# DMX_Control_Module.net
KiCad netlist of a schematic drawn in EAGLE
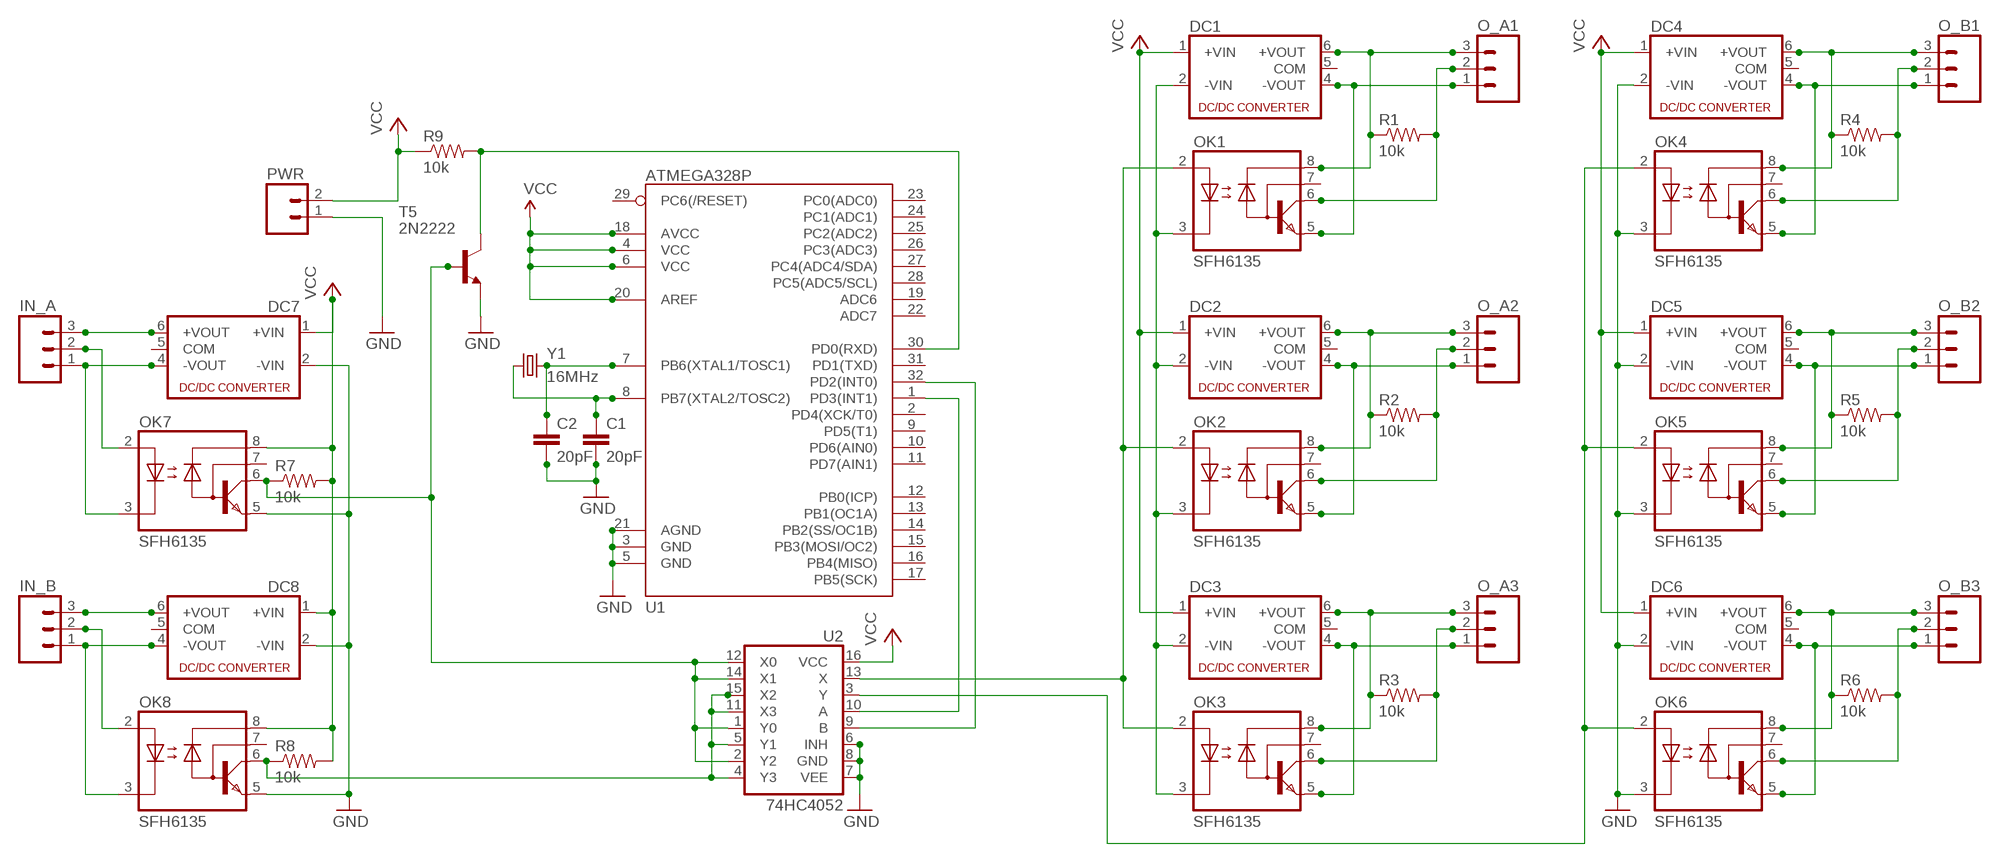
[diagram p0: schematic, sheet 1]

(export (version "E")
  (design (tool "Eeschema 10.0.6"))
  (components
    (comp (ref "C1")
      (value "20pF")
      (footprint "eagle-import:CAP-PTH-SMALL")
      (libsource (lib "eagle-import") (part "CAPPTH"))
    )
    (comp (ref "C2")
      (value "20pF")
      (footprint "eagle-import:CAP-PTH-SMALL")
      (libsource (lib "eagle-import") (part "CAPPTH"))
    )
    (comp (ref "DC1")
      (value "NMA")
      (footprint "eagle-import:NMA")
      (fields (field (name "MF") "C & D TECHNOLOGIES, INC") (field (name "MPN") "NMA0515SC"))
      (libsource (lib "eagle-import") (part "NMA"))
    )
    (comp (ref "DC2")
      (value "NMA")
      (footprint "eagle-import:NMA")
      (fields (field (name "MF") "C & D TECHNOLOGIES, INC") (field (name "MPN") "NMA0515SC"))
      (libsource (lib "eagle-import") (part "NMA"))
    )
    (comp (ref "DC3")
      (value "NMA")
      (footprint "eagle-import:NMA")
      (fields (field (name "MF") "C & D TECHNOLOGIES, INC") (field (name "MPN") "NMA0515SC"))
      (libsource (lib "eagle-import") (part "NMA"))
    )
    (comp (ref "DC4")
      (value "NMA")
      (footprint "eagle-import:NMA")
      (fields (field (name "MF") "C & D TECHNOLOGIES, INC") (field (name "MPN") "NMA0515SC"))
      (libsource (lib "eagle-import") (part "NMA"))
    )
    (comp (ref "DC5")
      (value "NMA")
      (footprint "eagle-import:NMA")
      (fields (field (name "MF") "C & D TECHNOLOGIES, INC") (field (name "MPN") "NMA0515SC"))
      (libsource (lib "eagle-import") (part "NMA"))
    )
    (comp (ref "DC6")
      (value "NMA")
      (footprint "eagle-import:NMA")
      (fields (field (name "MF") "C & D TECHNOLOGIES, INC") (field (name "MPN") "NMA0515SC"))
      (libsource (lib "eagle-import") (part "NMA"))
    )
    (comp (ref "DC7")
      (value "NMA")
      (footprint "eagle-import:NMA")
      (fields (field (name "MF") "C & D TECHNOLOGIES, INC") (field (name "MPN") "NMA0515SC"))
      (libsource (lib "eagle-import") (part "NMA"))
    )
    (comp (ref "DC8")
      (value "NMA")
      (footprint "eagle-import:NMA")
      (fields (field (name "MF") "C & D TECHNOLOGIES, INC") (field (name "MPN") "NMA0515SC"))
      (libsource (lib "eagle-import") (part "NMA"))
    )
    (comp (ref "IN_A")
      (value "M03PTH")
      (footprint "eagle-import:1X03")
      (libsource (lib "eagle-import") (part "M03PTH"))
    )
    (comp (ref "IN_B")
      (value "M03PTH")
      (footprint "eagle-import:1X03")
      (libsource (lib "eagle-import") (part "M03PTH"))
    )
    (comp (ref "OK1")
      (value "SFH6135")
      (footprint "eagle-import:DIL08")
      (fields (field (name "MF") "FAIRCHILD SEMICONDUCTOR") (field (name "MPN") "6N135"))
      (libsource (lib "eagle-import") (part "6N135"))
    )
    (comp (ref "OK2")
      (value "SFH6135")
      (footprint "eagle-import:DIL08")
      (fields (field (name "MF") "FAIRCHILD SEMICONDUCTOR") (field (name "MPN") "6N135"))
      (libsource (lib "eagle-import") (part "6N135"))
    )
    (comp (ref "OK3")
      (value "SFH6135")
      (footprint "eagle-import:DIL08")
      (fields (field (name "MF") "FAIRCHILD SEMICONDUCTOR") (field (name "MPN") "6N135"))
      (libsource (lib "eagle-import") (part "6N135"))
    )
    (comp (ref "OK4")
      (value "SFH6135")
      (footprint "eagle-import:DIL08")
      (fields (field (name "MF") "FAIRCHILD SEMICONDUCTOR") (field (name "MPN") "6N135"))
      (libsource (lib "eagle-import") (part "6N135"))
    )
    (comp (ref "OK5")
      (value "SFH6135")
      (footprint "eagle-import:DIL08")
      (fields (field (name "MF") "FAIRCHILD SEMICONDUCTOR") (field (name "MPN") "6N135"))
      (libsource (lib "eagle-import") (part "6N135"))
    )
    (comp (ref "OK6")
      (value "SFH6135")
      (footprint "eagle-import:DIL08")
      (fields (field (name "MF") "FAIRCHILD SEMICONDUCTOR") (field (name "MPN") "6N135"))
      (libsource (lib "eagle-import") (part "6N135"))
    )
    (comp (ref "OK7")
      (value "SFH6135")
      (footprint "eagle-import:DIL08")
      (fields (field (name "MF") "FAIRCHILD SEMICONDUCTOR") (field (name "MPN") "6N135"))
      (libsource (lib "eagle-import") (part "6N135"))
    )
    (comp (ref "OK8")
      (value "SFH6135")
      (footprint "eagle-import:DIL08")
      (fields (field (name "MF") "FAIRCHILD SEMICONDUCTOR") (field (name "MPN") "6N135"))
      (libsource (lib "eagle-import") (part "6N135"))
    )
    (comp (ref "O_A1")
      (value "M03PTH")
      (footprint "eagle-import:1X03")
      (libsource (lib "eagle-import") (part "M03PTH"))
    )
    (comp (ref "O_A2")
      (value "M03PTH")
      (footprint "eagle-import:1X03")
      (libsource (lib "eagle-import") (part "M03PTH"))
    )
    (comp (ref "O_A3")
      (value "M03PTH")
      (footprint "eagle-import:1X03")
      (libsource (lib "eagle-import") (part "M03PTH"))
    )
    (comp (ref "O_B1")
      (value "M03PTH")
      (footprint "eagle-import:1X03")
      (libsource (lib "eagle-import") (part "M03PTH"))
    )
    (comp (ref "O_B2")
      (value "M03PTH")
      (footprint "eagle-import:1X03")
      (libsource (lib "eagle-import") (part "M03PTH"))
    )
    (comp (ref "O_B3")
      (value "M03PTH")
      (footprint "eagle-import:1X03")
      (libsource (lib "eagle-import") (part "M03PTH"))
    )
    (comp (ref "PWR")
      (value "M02PTH")
      (footprint "eagle-import:1X02")
      (libsource (lib "eagle-import") (part "M02PTH"))
    )
    (comp (ref "R1")
      (value "10k")
      (footprint "eagle-import:AXIAL-0.4")
      (libsource (lib "eagle-import") (part "RESISTORPTH-1/4W"))
    )
    (comp (ref "R2")
      (value "10k")
      (footprint "eagle-import:AXIAL-0.4")
      (libsource (lib "eagle-import") (part "RESISTORPTH-1/4W"))
    )
    (comp (ref "R3")
      (value "10k")
      (footprint "eagle-import:AXIAL-0.4")
      (libsource (lib "eagle-import") (part "RESISTORPTH-1/4W"))
    )
    (comp (ref "R4")
      (value "10k")
      (footprint "eagle-import:AXIAL-0.4")
      (libsource (lib "eagle-import") (part "RESISTORPTH-1/4W"))
    )
    (comp (ref "R5")
      (value "10k")
      (footprint "eagle-import:AXIAL-0.4")
      (libsource (lib "eagle-import") (part "RESISTORPTH-1/4W"))
    )
    (comp (ref "R6")
      (value "10k")
      (footprint "eagle-import:AXIAL-0.4")
      (libsource (lib "eagle-import") (part "RESISTORPTH-1/4W"))
    )
    (comp (ref "R7")
      (value "10k")
      (footprint "eagle-import:AXIAL-0.4")
      (libsource (lib "eagle-import") (part "RESISTORPTH-1/4W"))
    )
    (comp (ref "R8")
      (value "10k")
      (footprint "eagle-import:AXIAL-0.4")
      (libsource (lib "eagle-import") (part "RESISTORPTH-1/4W"))
    )
    (comp (ref "R9")
      (value "10k")
      (footprint "eagle-import:AXIAL-0.4")
      (libsource (lib "eagle-import") (part "RESISTORPTH-1/4W"))
    )
    (comp (ref "T5")
      (value "2N2222")
      (footprint "eagle-import:TO92")
      (libsource (lib "eagle-import") (part "-NPN-TO92"))
    )
    (comp (ref "U1")
      (value "ATMEGA328P")
      (footprint "eagle-import:TQFP32-08")
      (libsource (lib "eagle-import") (part "ATMEGA328_SMT"))
    )
    (comp (ref "U2")
      (value "74HC4052")
      (footprint "eagle-import:DIL16")
      (libsource (lib "eagle-import") (part "74HC4052DIP"))
    )
    (comp (ref "Y1")
      (value "16MHz")
      (footprint "eagle-import:HC49US")
      (libsource (lib "eagle-import") (part "CRYSTALHC49US"))
    )
  )
  (nets
    (net (code "1") (name "GND") (class "Default")
      (node (ref "C1") (pin "2") (pinfunction "2_2") (pintype "passive"))
      (node (ref "C2") (pin "2") (pinfunction "2_2") (pintype "passive"))
      (node (ref "DC4") (pin "2") (pinfunction "-VIN_2") (pintype "passive"))
      (node (ref "DC5") (pin "2") (pinfunction "-VIN_2") (pintype "passive"))
      (node (ref "DC6") (pin "2") (pinfunction "-VIN_2") (pintype "passive"))
      (node (ref "DC7") (pin "2") (pinfunction "-VIN_2") (pintype "passive"))
      (node (ref "DC8") (pin "2") (pinfunction "-VIN_2") (pintype "passive"))
      (node (ref "OK4") (pin "3") (pinfunction "C_3") (pintype "passive"))
      (node (ref "OK5") (pin "3") (pinfunction "C_3") (pintype "passive"))
      (node (ref "OK6") (pin "3") (pinfunction "C_3") (pintype "passive"))
      (node (ref "OK7") (pin "5") (pinfunction "GND_5") (pintype "passive"))
      (node (ref "OK8") (pin "5") (pinfunction "GND_5") (pintype "passive"))
      (node (ref "PWR") (pin "1") (pinfunction "1_1") (pintype "passive"))
      (node (ref "T5") (pin "1") (pinfunction "E_1") (pintype "passive"))
      (node (ref "U1") (pin "21") (pinfunction "AGND_21") (pintype "bidirectional"))
      (node (ref "U1") (pin "3") (pinfunction "GND_3") (pintype "bidirectional"))
      (node (ref "U1") (pin "5") (pinfunction "GND_5") (pintype "bidirectional"))
      (node (ref "U2") (pin "6") (pinfunction "INH_6") (pintype "input"))
      (node (ref "U2") (pin "7") (pinfunction "VEE_7") (pintype "power_in"))
      (node (ref "U2") (pin "8") (pinfunction "GND_8") (pintype "power_in"))
    )
    (net (code "2") (name "Net-(DC1-+VOUT)") (class "Default")
      (node (ref "DC1") (pin "6") (pinfunction "+VOUT_6") (pintype "passive"))
      (node (ref "OK1") (pin "8") (pinfunction "VCC_8") (pintype "passive"))
      (node (ref "O_A1") (pin "3") (pinfunction "3_3") (pintype "passive"))
      (node (ref "R1") (pin "P$1") (pinfunction "1_P$1") (pintype "passive"))
    )
    (net (code "3") (name "Net-(DC1--VIN)") (class "Default")
      (node (ref "DC1") (pin "2") (pinfunction "-VIN_2") (pintype "passive"))
      (node (ref "DC2") (pin "2") (pinfunction "-VIN_2") (pintype "passive"))
      (node (ref "DC3") (pin "2") (pinfunction "-VIN_2") (pintype "passive"))
      (node (ref "OK1") (pin "3") (pinfunction "C_3") (pintype "passive"))
      (node (ref "OK2") (pin "3") (pinfunction "C_3") (pintype "passive"))
      (node (ref "OK3") (pin "3") (pinfunction "C_3") (pintype "passive"))
    )
    (net (code "4") (name "Net-(DC1--VOUT)") (class "Default")
      (node (ref "DC1") (pin "4") (pinfunction "-VOUT_4") (pintype "passive"))
      (node (ref "OK1") (pin "5") (pinfunction "GND_5") (pintype "passive"))
      (node (ref "O_A1") (pin "1") (pinfunction "1_1") (pintype "passive"))
    )
    (net (code "5") (name "Net-(DC2-+VOUT)") (class "Default")
      (node (ref "DC2") (pin "6") (pinfunction "+VOUT_6") (pintype "passive"))
      (node (ref "OK2") (pin "8") (pinfunction "VCC_8") (pintype "passive"))
      (node (ref "O_A2") (pin "3") (pinfunction "3_3") (pintype "passive"))
      (node (ref "R2") (pin "P$1") (pinfunction "1_P$1") (pintype "passive"))
    )
    (net (code "6") (name "Net-(DC2--VOUT)") (class "Default")
      (node (ref "DC2") (pin "4") (pinfunction "-VOUT_4") (pintype "passive"))
      (node (ref "OK2") (pin "5") (pinfunction "GND_5") (pintype "passive"))
      (node (ref "O_A2") (pin "1") (pinfunction "1_1") (pintype "passive"))
    )
    (net (code "7") (name "Net-(DC3-+VOUT)") (class "Default")
      (node (ref "DC3") (pin "6") (pinfunction "+VOUT_6") (pintype "passive"))
      (node (ref "OK3") (pin "8") (pinfunction "VCC_8") (pintype "passive"))
      (node (ref "O_A3") (pin "3") (pinfunction "3_3") (pintype "passive"))
      (node (ref "R3") (pin "P$1") (pinfunction "1_P$1") (pintype "passive"))
    )
    (net (code "8") (name "Net-(DC3--VOUT)") (class "Default")
      (node (ref "DC3") (pin "4") (pinfunction "-VOUT_4") (pintype "passive"))
      (node (ref "OK3") (pin "5") (pinfunction "GND_5") (pintype "passive"))
      (node (ref "O_A3") (pin "1") (pinfunction "1_1") (pintype "passive"))
    )
    (net (code "9") (name "Net-(DC4-+VOUT)") (class "Default")
      (node (ref "DC4") (pin "6") (pinfunction "+VOUT_6") (pintype "passive"))
      (node (ref "OK4") (pin "8") (pinfunction "VCC_8") (pintype "passive"))
      (node (ref "O_B1") (pin "3") (pinfunction "3_3") (pintype "passive"))
      (node (ref "R4") (pin "P$1") (pinfunction "1_P$1") (pintype "passive"))
    )
    (net (code "10") (name "Net-(DC4--VOUT)") (class "Default")
      (node (ref "DC4") (pin "4") (pinfunction "-VOUT_4") (pintype "passive"))
      (node (ref "OK4") (pin "5") (pinfunction "GND_5") (pintype "passive"))
      (node (ref "O_B1") (pin "1") (pinfunction "1_1") (pintype "passive"))
    )
    (net (code "11") (name "Net-(DC5-+VOUT)") (class "Default")
      (node (ref "DC5") (pin "6") (pinfunction "+VOUT_6") (pintype "passive"))
      (node (ref "OK5") (pin "8") (pinfunction "VCC_8") (pintype "passive"))
      (node (ref "O_B2") (pin "3") (pinfunction "3_3") (pintype "passive"))
      (node (ref "R5") (pin "P$1") (pinfunction "1_P$1") (pintype "passive"))
    )
    (net (code "12") (name "Net-(DC5--VOUT)") (class "Default")
      (node (ref "DC5") (pin "4") (pinfunction "-VOUT_4") (pintype "passive"))
      (node (ref "OK5") (pin "5") (pinfunction "GND_5") (pintype "passive"))
      (node (ref "O_B2") (pin "1") (pinfunction "1_1") (pintype "passive"))
    )
    (net (code "13") (name "Net-(DC6-+VOUT)") (class "Default")
      (node (ref "DC6") (pin "6") (pinfunction "+VOUT_6") (pintype "passive"))
      (node (ref "OK6") (pin "8") (pinfunction "VCC_8") (pintype "passive"))
      (node (ref "O_B3") (pin "3") (pinfunction "3_3") (pintype "passive"))
      (node (ref "R6") (pin "P$1") (pinfunction "1_P$1") (pintype "passive"))
    )
    (net (code "14") (name "Net-(DC6--VOUT)") (class "Default")
      (node (ref "DC6") (pin "4") (pinfunction "-VOUT_4") (pintype "passive"))
      (node (ref "OK6") (pin "5") (pinfunction "GND_5") (pintype "passive"))
      (node (ref "O_B3") (pin "1") (pinfunction "1_1") (pintype "passive"))
    )
    (net (code "15") (name "Net-(DC7-+VOUT)") (class "Default")
      (node (ref "DC7") (pin "6") (pinfunction "+VOUT_6") (pintype "passive"))
      (node (ref "IN_A") (pin "3") (pinfunction "3_3") (pintype "passive"))
    )
    (net (code "16") (name "Net-(DC7--VOUT)") (class "Default")
      (node (ref "DC7") (pin "4") (pinfunction "-VOUT_4") (pintype "passive"))
      (node (ref "IN_A") (pin "1") (pinfunction "1_1") (pintype "passive"))
      (node (ref "OK7") (pin "3") (pinfunction "C_3") (pintype "passive"))
    )
    (net (code "17") (name "Net-(DC8-+VOUT)") (class "Default")
      (node (ref "DC8") (pin "6") (pinfunction "+VOUT_6") (pintype "passive"))
      (node (ref "IN_B") (pin "3") (pinfunction "3_3") (pintype "passive"))
    )
    (net (code "18") (name "Net-(DC8--VOUT)") (class "Default")
      (node (ref "DC8") (pin "4") (pinfunction "-VOUT_4") (pintype "passive"))
      (node (ref "IN_B") (pin "1") (pinfunction "1_1") (pintype "passive"))
      (node (ref "OK8") (pin "3") (pinfunction "C_3") (pintype "passive"))
    )
    (net (code "19") (name "Net-(OK1-A)") (class "Default")
      (node (ref "OK1") (pin "2") (pinfunction "A_2") (pintype "passive"))
      (node (ref "OK2") (pin "2") (pinfunction "A_2") (pintype "passive"))
      (node (ref "OK3") (pin "2") (pinfunction "A_2") (pintype "passive"))
      (node (ref "U2") (pin "13") (pinfunction "X_13") (pintype "bidirectional"))
    )
    (net (code "20") (name "Net-(OK1-VO)") (class "Default")
      (node (ref "OK1") (pin "6") (pinfunction "VO_6") (pintype "passive"))
      (node (ref "O_A1") (pin "2") (pinfunction "2_2") (pintype "passive"))
      (node (ref "R1") (pin "P$2") (pinfunction "2_P$2") (pintype "passive"))
    )
    (net (code "21") (name "Net-(OK2-VO)") (class "Default")
      (node (ref "OK2") (pin "6") (pinfunction "VO_6") (pintype "passive"))
      (node (ref "O_A2") (pin "2") (pinfunction "2_2") (pintype "passive"))
      (node (ref "R2") (pin "P$2") (pinfunction "2_P$2") (pintype "passive"))
    )
    (net (code "22") (name "Net-(OK3-VO)") (class "Default")
      (node (ref "OK3") (pin "6") (pinfunction "VO_6") (pintype "passive"))
      (node (ref "O_A3") (pin "2") (pinfunction "2_2") (pintype "passive"))
      (node (ref "R3") (pin "P$2") (pinfunction "2_P$2") (pintype "passive"))
    )
    (net (code "23") (name "Net-(OK4-A)") (class "Default")
      (node (ref "OK4") (pin "2") (pinfunction "A_2") (pintype "passive"))
      (node (ref "OK5") (pin "2") (pinfunction "A_2") (pintype "passive"))
      (node (ref "OK6") (pin "2") (pinfunction "A_2") (pintype "passive"))
      (node (ref "U2") (pin "3") (pinfunction "Y_3") (pintype "bidirectional"))
    )
    (net (code "24") (name "Net-(OK4-VO)") (class "Default")
      (node (ref "OK4") (pin "6") (pinfunction "VO_6") (pintype "passive"))
      (node (ref "O_B1") (pin "2") (pinfunction "2_2") (pintype "passive"))
      (node (ref "R4") (pin "P$2") (pinfunction "2_P$2") (pintype "passive"))
    )
    (net (code "25") (name "Net-(OK5-VO)") (class "Default")
      (node (ref "OK5") (pin "6") (pinfunction "VO_6") (pintype "passive"))
      (node (ref "O_B2") (pin "2") (pinfunction "2_2") (pintype "passive"))
      (node (ref "R5") (pin "P$2") (pinfunction "2_P$2") (pintype "passive"))
    )
    (net (code "26") (name "Net-(OK6-VO)") (class "Default")
      (node (ref "OK6") (pin "6") (pinfunction "VO_6") (pintype "passive"))
      (node (ref "O_B3") (pin "2") (pinfunction "2_2") (pintype "passive"))
      (node (ref "R6") (pin "P$2") (pinfunction "2_P$2") (pintype "passive"))
    )
    (net (code "27") (name "Net-(OK7-A)") (class "Default")
      (node (ref "IN_A") (pin "2") (pinfunction "2_2") (pintype "passive"))
      (node (ref "OK7") (pin "2") (pinfunction "A_2") (pintype "passive"))
    )
    (net (code "28") (name "Net-(OK7-VO)") (class "Default")
      (node (ref "OK7") (pin "6") (pinfunction "VO_6") (pintype "passive"))
      (node (ref "R7") (pin "P$1") (pinfunction "1_P$1") (pintype "passive"))
      (node (ref "T5") (pin "2") (pinfunction "B_2") (pintype "passive"))
      (node (ref "U2") (pin "1") (pinfunction "Y0_1") (pintype "bidirectional"))
      (node (ref "U2") (pin "12") (pinfunction "X0_12") (pintype "bidirectional"))
      (node (ref "U2") (pin "14") (pinfunction "X1_14") (pintype "bidirectional"))
      (node (ref "U2") (pin "2") (pinfunction "Y2_2") (pintype "bidirectional"))
    )
    (net (code "29") (name "Net-(OK8-A)") (class "Default")
      (node (ref "IN_B") (pin "2") (pinfunction "2_2") (pintype "passive"))
      (node (ref "OK8") (pin "2") (pinfunction "A_2") (pintype "passive"))
    )
    (net (code "30") (name "Net-(OK8-VO)") (class "Default")
      (node (ref "OK8") (pin "6") (pinfunction "VO_6") (pintype "passive"))
      (node (ref "R8") (pin "P$1") (pinfunction "1_P$1") (pintype "passive"))
      (node (ref "U2") (pin "11") (pinfunction "X3_11") (pintype "bidirectional"))
      (node (ref "U2") (pin "15") (pinfunction "X2_15") (pintype "bidirectional"))
      (node (ref "U2") (pin "4") (pinfunction "Y3_4") (pintype "bidirectional"))
      (node (ref "U2") (pin "5") (pinfunction "Y1_5") (pintype "bidirectional"))
    )
    (net (code "31") (name "Net-(R9-2)") (class "Default")
      (node (ref "R9") (pin "P$2") (pinfunction "2_P$2") (pintype "passive"))
      (node (ref "T5") (pin "3") (pinfunction "C_3") (pintype "passive"))
      (node (ref "U1") (pin "30") (pinfunction "PD0(RXD)_30") (pintype "bidirectional"))
    )
    (net (code "32") (name "Net-(U1-PB6(XTAL1{slash}TOSC1))") (class "Default")
      (node (ref "C2") (pin "1") (pinfunction "1_1") (pintype "passive"))
      (node (ref "U1") (pin "7") (pinfunction "PB6(XTAL1/TOSC1)_7") (pintype "bidirectional"))
      (node (ref "Y1") (pin "2") (pinfunction "2_2") (pintype "passive"))
    )
    (net (code "33") (name "Net-(U1-PB7(XTAL2{slash}TOSC2))") (class "Default")
      (node (ref "C1") (pin "1") (pinfunction "1_1") (pintype "passive"))
      (node (ref "U1") (pin "8") (pinfunction "PB7(XTAL2/TOSC2)_8") (pintype "bidirectional"))
      (node (ref "Y1") (pin "1") (pinfunction "1_1") (pintype "passive"))
    )
    (net (code "34") (name "Net-(U1-PD2(INT0))") (class "Default")
      (node (ref "U1") (pin "32") (pinfunction "PD2(INT0)_32") (pintype "bidirectional"))
      (node (ref "U2") (pin "9") (pinfunction "B_9") (pintype "input"))
    )
    (net (code "35") (name "Net-(U1-PD3(INT1))") (class "Default")
      (node (ref "U1") (pin "1") (pinfunction "PD3(INT1)_1") (pintype "bidirectional"))
      (node (ref "U2") (pin "10") (pinfunction "A_10") (pintype "input"))
    )
    (net (code "36") (name "VCC") (class "Default")
      (node (ref "DC1") (pin "1") (pinfunction "+VIN_1") (pintype "passive"))
      (node (ref "DC2") (pin "1") (pinfunction "+VIN_1") (pintype "passive"))
      (node (ref "DC3") (pin "1") (pinfunction "+VIN_1") (pintype "passive"))
      (node (ref "DC4") (pin "1") (pinfunction "+VIN_1") (pintype "passive"))
      (node (ref "DC5") (pin "1") (pinfunction "+VIN_1") (pintype "passive"))
      (node (ref "DC6") (pin "1") (pinfunction "+VIN_1") (pintype "passive"))
      (node (ref "DC7") (pin "1") (pinfunction "+VIN_1") (pintype "passive"))
      (node (ref "DC8") (pin "1") (pinfunction "+VIN_1") (pintype "passive"))
      (node (ref "OK7") (pin "8") (pinfunction "VCC_8") (pintype "passive"))
      (node (ref "OK8") (pin "8") (pinfunction "VCC_8") (pintype "passive"))
      (node (ref "PWR") (pin "2") (pinfunction "2_2") (pintype "passive"))
      (node (ref "R7") (pin "P$2") (pinfunction "2_P$2") (pintype "passive"))
      (node (ref "R8") (pin "P$2") (pinfunction "2_P$2") (pintype "passive"))
      (node (ref "R9") (pin "P$1") (pinfunction "1_P$1") (pintype "passive"))
      (node (ref "U1") (pin "18") (pinfunction "AVCC_18") (pintype "bidirectional"))
      (node (ref "U1") (pin "20") (pinfunction "AREF_20") (pintype "bidirectional"))
      (node (ref "U1") (pin "4") (pinfunction "VCC_4") (pintype "bidirectional"))
      (node (ref "U1") (pin "6") (pinfunction "VCC_6") (pintype "bidirectional"))
      (node (ref "U2") (pin "16") (pinfunction "VCC_16") (pintype "power_in"))
    )
    (net (code "37") (name "unconnected-(DC1-COM-Pad5)") (class "Default")
      (node (ref "DC1") (pin "5") (pinfunction "COM_5") (pintype "passive"))
    )
    (net (code "38") (name "unconnected-(DC2-COM-Pad5)") (class "Default")
      (node (ref "DC2") (pin "5") (pinfunction "COM_5") (pintype "passive"))
    )
    (net (code "39") (name "unconnected-(DC3-COM-Pad5)") (class "Default")
      (node (ref "DC3") (pin "5") (pinfunction "COM_5") (pintype "passive"))
    )
    (net (code "40") (name "unconnected-(DC4-COM-Pad5)") (class "Default")
      (node (ref "DC4") (pin "5") (pinfunction "COM_5") (pintype "passive"))
    )
    (net (code "41") (name "unconnected-(DC5-COM-Pad5)") (class "Default")
      (node (ref "DC5") (pin "5") (pinfunction "COM_5") (pintype "passive"))
    )
    (net (code "42") (name "unconnected-(DC6-COM-Pad5)") (class "Default")
      (node (ref "DC6") (pin "5") (pinfunction "COM_5") (pintype "passive"))
    )
    (net (code "43") (name "unconnected-(DC7-COM-Pad5)") (class "Default")
      (node (ref "DC7") (pin "5") (pinfunction "COM_5") (pintype "passive"))
    )
    (net (code "44") (name "unconnected-(DC8-COM-Pad5)") (class "Default")
      (node (ref "DC8") (pin "5") (pinfunction "COM_5") (pintype "passive"))
    )
    (net (code "45") (name "unconnected-(OK1-VB-Pad7)") (class "Default")
      (node (ref "OK1") (pin "7") (pinfunction "VB_7") (pintype "passive"))
    )
    (net (code "46") (name "unconnected-(OK2-VB-Pad7)") (class "Default")
      (node (ref "OK2") (pin "7") (pinfunction "VB_7") (pintype "passive"))
    )
    (net (code "47") (name "unconnected-(OK3-VB-Pad7)") (class "Default")
      (node (ref "OK3") (pin "7") (pinfunction "VB_7") (pintype "passive"))
    )
    (net (code "48") (name "unconnected-(OK4-VB-Pad7)") (class "Default")
      (node (ref "OK4") (pin "7") (pinfunction "VB_7") (pintype "passive"))
    )
    (net (code "49") (name "unconnected-(OK5-VB-Pad7)") (class "Default")
      (node (ref "OK5") (pin "7") (pinfunction "VB_7") (pintype "passive"))
    )
    (net (code "50") (name "unconnected-(OK6-VB-Pad7)") (class "Default")
      (node (ref "OK6") (pin "7") (pinfunction "VB_7") (pintype "passive"))
    )
    (net (code "51") (name "unconnected-(OK7-VB-Pad7)") (class "Default")
      (node (ref "OK7") (pin "7") (pinfunction "VB_7") (pintype "passive"))
    )
    (net (code "52") (name "unconnected-(OK8-VB-Pad7)") (class "Default")
      (node (ref "OK8") (pin "7") (pinfunction "VB_7") (pintype "passive"))
    )
    (net (code "53") (name "unconnected-(U1-ADC6-Pad19)") (class "Default")
      (node (ref "U1") (pin "19") (pinfunction "ADC6_19") (pintype "bidirectional"))
    )
    (net (code "54") (name "unconnected-(U1-ADC7-Pad22)") (class "Default")
      (node (ref "U1") (pin "22") (pinfunction "ADC7_22") (pintype "bidirectional"))
    )
    (net (code "55") (name "unconnected-(U1-PB0(ICP)-Pad12)") (class "Default")
      (node (ref "U1") (pin "12") (pinfunction "PB0(ICP)_12") (pintype "bidirectional"))
    )
    (net (code "56") (name "unconnected-(U1-PB1(OC1A)-Pad13)") (class "Default")
      (node (ref "U1") (pin "13") (pinfunction "PB1(OC1A)_13") (pintype "bidirectional"))
    )
    (net (code "57") (name "unconnected-(U1-PB2(SS{slash}OC1B)-Pad14)") (class "Default")
      (node (ref "U1") (pin "14") (pinfunction "PB2(SS/OC1B)_14") (pintype "bidirectional"))
    )
    (net (code "58") (name "unconnected-(U1-PB3(MOSI{slash}OC2)-Pad15)") (class "Default")
      (node (ref "U1") (pin "15") (pinfunction "PB3(MOSI/OC2)_15") (pintype "bidirectional"))
    )
    (net (code "59") (name "unconnected-(U1-PB4(MISO)-Pad16)") (class "Default")
      (node (ref "U1") (pin "16") (pinfunction "PB4(MISO)_16") (pintype "bidirectional"))
    )
    (net (code "60") (name "unconnected-(U1-PB5(SCK)-Pad17)") (class "Default")
      (node (ref "U1") (pin "17") (pinfunction "PB5(SCK)_17") (pintype "bidirectional"))
    )
    (net (code "61") (name "unconnected-(U1-PC0(ADC0)-Pad23)") (class "Default")
      (node (ref "U1") (pin "23") (pinfunction "PC0(ADC0)_23") (pintype "bidirectional"))
    )
    (net (code "62") (name "unconnected-(U1-PC1(ADC1)-Pad24)") (class "Default")
      (node (ref "U1") (pin "24") (pinfunction "PC1(ADC1)_24") (pintype "bidirectional"))
    )
    (net (code "63") (name "unconnected-(U1-PC2(ADC2)-Pad25)") (class "Default")
      (node (ref "U1") (pin "25") (pinfunction "PC2(ADC2)_25") (pintype "bidirectional"))
    )
    (net (code "64") (name "unconnected-(U1-PC3(ADC3)-Pad26)") (class "Default")
      (node (ref "U1") (pin "26") (pinfunction "PC3(ADC3)_26") (pintype "bidirectional"))
    )
    (net (code "65") (name "unconnected-(U1-PC4(ADC4{slash}SDA)-Pad27)") (class "Default")
      (node (ref "U1") (pin "27") (pinfunction "PC4(ADC4/SDA)_27") (pintype "bidirectional"))
    )
    (net (code "66") (name "unconnected-(U1-PC5(ADC5{slash}SCL)-Pad28)") (class "Default")
      (node (ref "U1") (pin "28") (pinfunction "PC5(ADC5/SCL)_28") (pintype "bidirectional"))
    )
    (net (code "67") (name "unconnected-(U1-PC6({slash}RESET)-Pad29)") (class "Default")
      (node (ref "U1") (pin "29") (pinfunction "PC6(/RESET)_29") (pintype "bidirectional"))
    )
    (net (code "68") (name "unconnected-(U1-PD1(TXD)-Pad31)") (class "Default")
      (node (ref "U1") (pin "31") (pinfunction "PD1(TXD)_31") (pintype "bidirectional"))
    )
    (net (code "69") (name "unconnected-(U1-PD4(XCK{slash}T0)-Pad2)") (class "Default")
      (node (ref "U1") (pin "2") (pinfunction "PD4(XCK/T0)_2") (pintype "bidirectional"))
    )
    (net (code "70") (name "unconnected-(U1-PD5(T1)-Pad9)") (class "Default")
      (node (ref "U1") (pin "9") (pinfunction "PD5(T1)_9") (pintype "bidirectional"))
    )
    (net (code "71") (name "unconnected-(U1-PD6(AIN0)-Pad10)") (class "Default")
      (node (ref "U1") (pin "10") (pinfunction "PD6(AIN0)_10") (pintype "bidirectional"))
    )
    (net (code "72") (name "unconnected-(U1-PD7(AIN1)-Pad11)") (class "Default")
      (node (ref "U1") (pin "11") (pinfunction "PD7(AIN1)_11") (pintype "bidirectional"))
    )
  )
)
